# MCU.net
KiCad netlist of a schematic drawn in Altium Designer
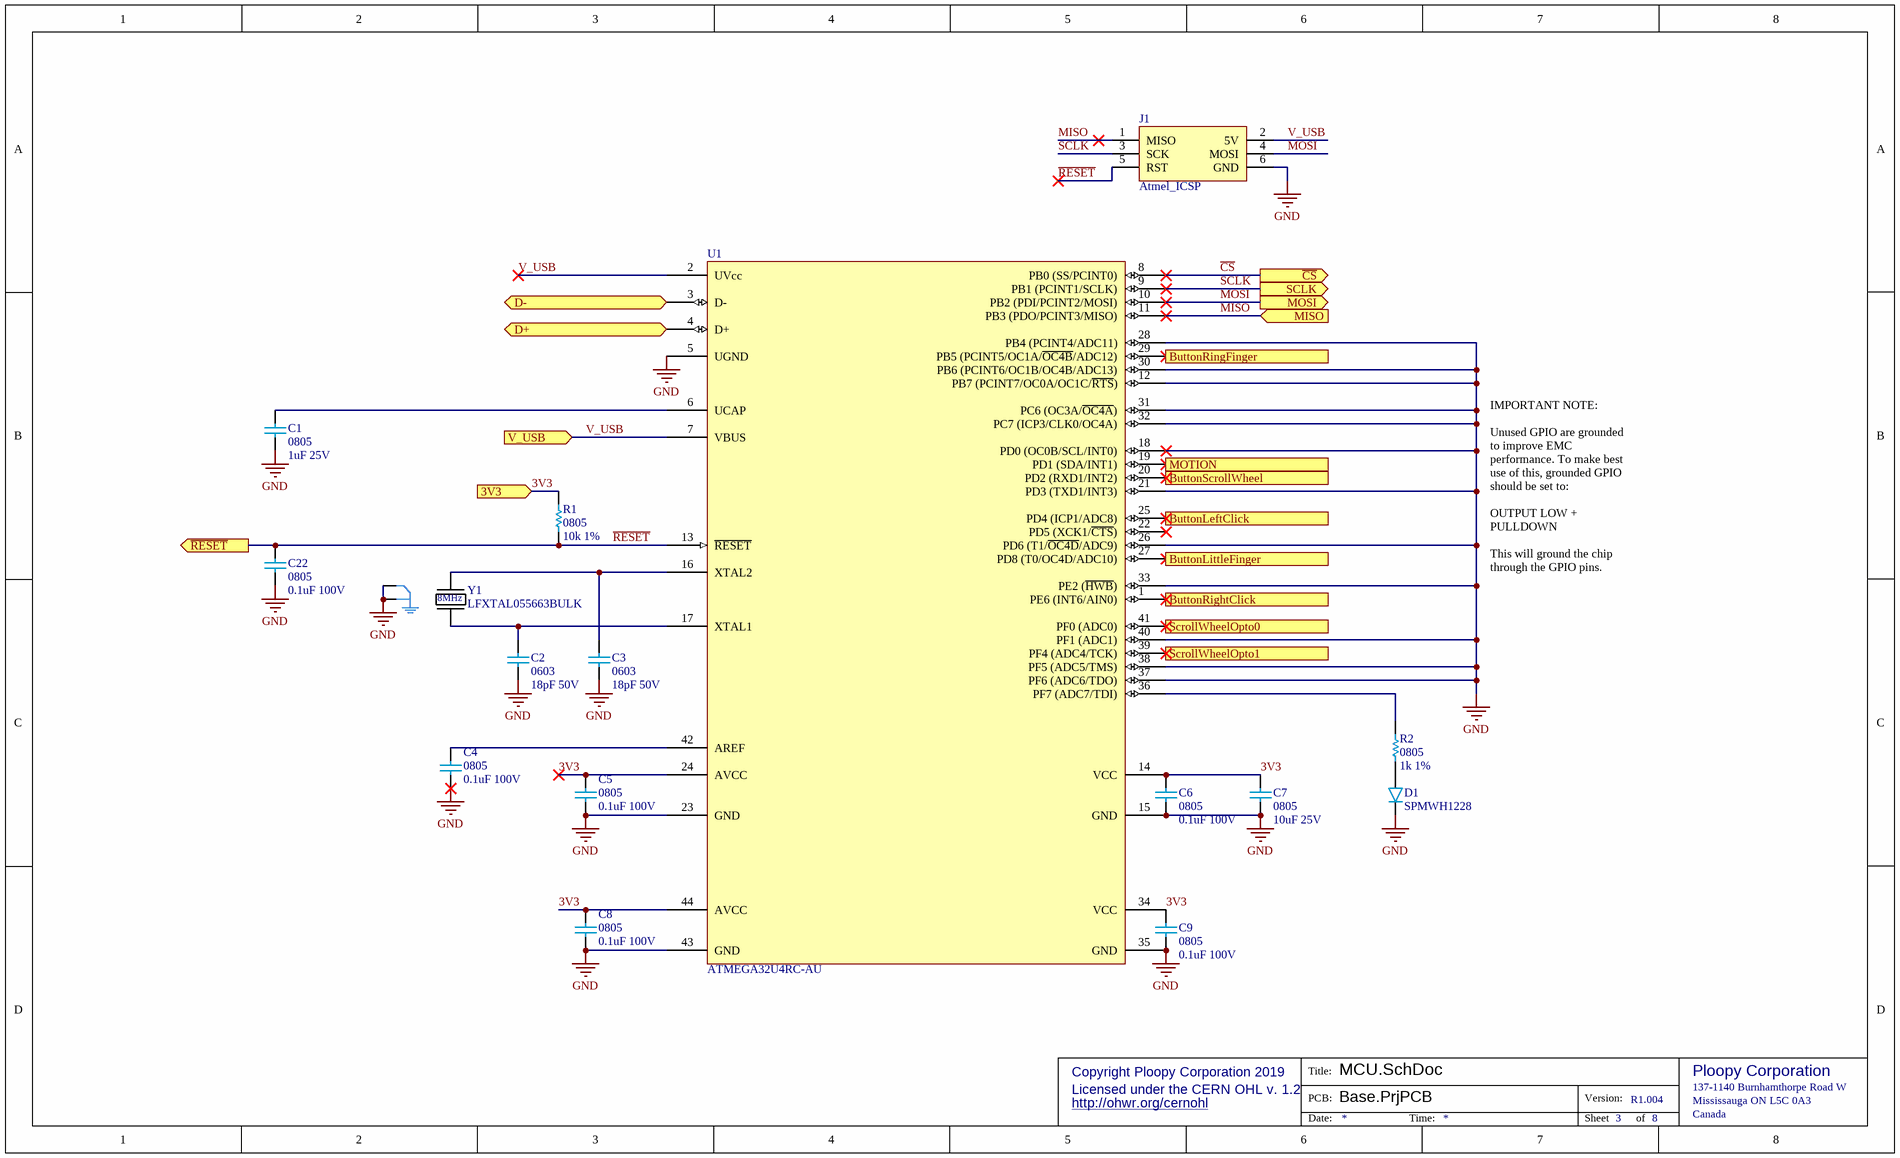
[diagram p0: MCU.SchDoc]

(export (version "E")
  (design (tool "Eeschema 10.0.6"))
  (components
    (comp (ref "C1")
      (value "0805")
      (footprint "0805")
      (description "0805, X5R or better")
      (fields (field (name "ALTIUM_VALUE") "1uF 25V"))
      (libsource (lib "Chip_Passives") (part "Cap 1uF 25V"))
    )
    (comp (ref "C2")
      (value "0603")
      (footprint "0603")
      (description "0603, C0G or better")
      (fields (field (name "ALTIUM_VALUE") "18pF 50V"))
      (libsource (lib "Chip_Passives") (part "Cap 18pF 50V"))
    )
    (comp (ref "C3")
      (value "0603")
      (footprint "0603")
      (description "0603, C0G or better")
      (fields (field (name "ALTIUM_VALUE") "18pF 50V"))
      (libsource (lib "Chip_Passives") (part "Cap 18pF 50V"))
    )
    (comp (ref "C4")
      (value "0805")
      (footprint "0805")
      (description "0805, X5R or better")
      (fields (field (name "ALTIUM_VALUE") "0.1uF 100V"))
      (libsource (lib "Chip_Passives") (part "Cap 0.1uF 100V"))
    )
    (comp (ref "C5")
      (value "0805")
      (footprint "0805")
      (description "0805, X5R or better")
      (fields (field (name "ALTIUM_VALUE") "0.1uF 100V"))
      (libsource (lib "Chip_Passives") (part "Cap 0.1uF 100V"))
    )
    (comp (ref "C6")
      (value "0805")
      (footprint "0805")
      (description "0805, X5R or better")
      (fields (field (name "ALTIUM_VALUE") "0.1uF 100V"))
      (libsource (lib "Chip_Passives") (part "Cap 0.1uF 100V"))
    )
    (comp (ref "C7")
      (value "0805")
      (footprint "0805")
      (description "0805, X5R or better")
      (fields (field (name "ALTIUM_VALUE") "10uF 25V"))
      (libsource (lib "Chip_Passives") (part "Cap 10uF 25V"))
    )
    (comp (ref "C8")
      (value "0805")
      (footprint "0805")
      (description "0805, X5R or better")
      (fields (field (name "ALTIUM_VALUE") "0.1uF 100V"))
      (libsource (lib "Chip_Passives") (part "Cap 0.1uF 100V"))
    )
    (comp (ref "C9")
      (value "0805")
      (footprint "0805")
      (description "0805, X5R or better")
      (fields (field (name "ALTIUM_VALUE") "0.1uF 100V"))
      (libsource (lib "Chip_Passives") (part "Cap 0.1uF 100V"))
    )
    (comp (ref "C22")
      (value "0805")
      (footprint "0805")
      (description "0805, X5R or better")
      (fields (field (name "ALTIUM_VALUE") "0.1uF 100V"))
      (libsource (lib "Chip_Passives") (part "Cap 0.1uF 100V"))
    )
    (comp (ref "D1")
      (value "SPMWH1228")
      (footprint "SPMWH1228")
      (description "3V/0.5W white LED, 2.8mm x 3.5mm")
      (libsource (lib "LEDs") (part "SPMWH1228"))
    )
    (comp (ref "J1")
      (value "Atmel_ICSP")
      (footprint "6x2")
      (description "6-pin 0.100\" ICSP header")
      (libsource (lib "Connectors") (part "Atmel_ICSP"))
    )
    (comp (ref "R1")
      (value "0805")
      (footprint "0805")
      (description "Chip resistor")
      (fields (field (name "ALTIUM_VALUE") "10k 1%"))
      (libsource (lib "Chip_Passives") (part "Res 10k 1% 0805"))
    )
    (comp (ref "R2")
      (value "0805")
      (footprint "0805")
      (description "Chip resistor, 1/8W 100PPM")
      (fields (field (name "ALTIUM_VALUE") "1k 1%"))
      (libsource (lib "Chip_Passives") (part "Res 1k 1% 0805"))
    )
    (comp (ref "U1")
      (value "ATMEGA32U4RC-AU")
      (footprint "ATmega32U4 - TQFP80P1200X1200X120-44N")
      (description "IC MCU 8BIT 32KB FLASH 44TQFP")
      (libsource (lib "MCUs") (part "ATMEGA32U4RC-AU"))
    )
    (comp (ref "Y1")
      (value "LFXTAL055663BULK")
      (footprint "LFXTAL055663BULK")
      (description "8MHz ±20ppm Crystal 18pF 150 Ohms 4-SMD, No Lead")
      (libsource (lib "Crystals") (part "LFXTAL055663BULK"))
    )
  )
  (nets
    (net (code "1") (name "/3V3") (class "Default")
      (node (ref "C5") (pin "2") (pinfunction "2_2") (pintype "passive"))
      (node (ref "C6") (pin "2") (pinfunction "2_2") (pintype "passive"))
      (node (ref "C7") (pin "2") (pinfunction "2_2") (pintype "passive"))
      (node (ref "C8") (pin "2") (pinfunction "2_2") (pintype "passive"))
      (node (ref "C9") (pin "2") (pinfunction "2_2") (pintype "passive"))
      (node (ref "R1") (pin "2") (pinfunction "2_2") (pintype "passive"))
      (node (ref "U1") (pin "14") (pinfunction "VCC_14") (pintype "power_in"))
      (node (ref "U1") (pin "24") (pinfunction "AVCC_24") (pintype "power_in"))
      (node (ref "U1") (pin "34") (pinfunction "VCC_34") (pintype "power_in"))
      (node (ref "U1") (pin "44") (pinfunction "AVCC_44") (pintype "power_in"))
    )
    (net (code "2") (name "/ButtonLeftClick") (class "Default")
      (node (ref "U1") (pin "25") (pinfunction "PD4_(ICP1/ADC8)_25") (pintype "bidirectional+no_connect"))
    )
    (net (code "3") (name "/ButtonLittleFinger") (class "Default")
      (node (ref "U1") (pin "27") (pinfunction "PD8_(T0/OC4D/ADC10)_27") (pintype "bidirectional+no_connect"))
    )
    (net (code "4") (name "/ButtonRightClick") (class "Default")
      (node (ref "U1") (pin "1") (pinfunction "PE6_(INT6/AIN0)_1") (pintype "bidirectional+no_connect"))
    )
    (net (code "5") (name "/ButtonRingFinger") (class "Default")
      (node (ref "U1") (pin "29") (pinfunction "PB5_(PCINT5/OC1A/~{OC4B}/ADC12)_29") (pintype "bidirectional+no_connect"))
    )
    (net (code "6") (name "/ButtonScrollWheel") (class "Default")
      (node (ref "U1") (pin "20") (pinfunction "PD2_(RXD1/INT2)_20") (pintype "bidirectional+no_connect"))
    )
    (net (code "7") (name "/D+") (class "Default")
      (node (ref "U1") (pin "4") (pinfunction "D+_4") (pintype "bidirectional"))
    )
    (net (code "8") (name "/D-") (class "Default")
      (node (ref "U1") (pin "3") (pinfunction "D-_3") (pintype "bidirectional"))
    )
    (net (code "9") (name "/MISO") (class "Default")
      (node (ref "J1") (pin "1") (pinfunction "MISO_1") (pintype "passive"))
      (node (ref "U1") (pin "11") (pinfunction "PB3_(PDO/PCINT3/MISO)_11") (pintype "bidirectional"))
    )
    (net (code "10") (name "/MOSI") (class "Default")
      (node (ref "J1") (pin "4") (pinfunction "MOSI_4") (pintype "passive"))
      (node (ref "U1") (pin "10") (pinfunction "PB2_(PDI/PCINT2/MOSI)_10") (pintype "bidirectional"))
    )
    (net (code "11") (name "/MOTION") (class "Default")
      (node (ref "U1") (pin "19") (pinfunction "PD1_(SDA/INT1)_19") (pintype "bidirectional+no_connect"))
    )
    (net (code "12") (name "/SCLK") (class "Default")
      (node (ref "J1") (pin "3") (pinfunction "SCK_3") (pintype "passive"))
      (node (ref "U1") (pin "9") (pinfunction "PB1_(PCINT1/SCLK)_9") (pintype "bidirectional"))
    )
    (net (code "13") (name "/ScrollWheelOpto0") (class "Default")
      (node (ref "U1") (pin "41") (pinfunction "PF0_(ADC0)_41") (pintype "bidirectional+no_connect"))
    )
    (net (code "14") (name "/ScrollWheelOpto1") (class "Default")
      (node (ref "U1") (pin "39") (pinfunction "PF4_(ADC4/TCK)_39") (pintype "bidirectional+no_connect"))
    )
    (net (code "15") (name "/V_USB") (class "Default")
      (node (ref "J1") (pin "2") (pinfunction "5V_2") (pintype "passive"))
      (node (ref "U1") (pin "2") (pinfunction "UVcc_2") (pintype "power_in"))
      (node (ref "U1") (pin "7") (pinfunction "VBUS_7") (pintype "power_in"))
    )
    (net (code "16") (name "/~{CS}") (class "Default")
      (node (ref "U1") (pin "8") (pinfunction "PB0_(SS/PCINT0)_8") (pintype "bidirectional+no_connect"))
    )
    (net (code "17") (name "/~{RESET}") (class "Default")
      (node (ref "C22") (pin "2") (pinfunction "2_2") (pintype "passive"))
      (node (ref "J1") (pin "5") (pinfunction "RST_5") (pintype "passive"))
      (node (ref "R1") (pin "1") (pinfunction "1_1") (pintype "passive"))
      (node (ref "U1") (pin "13") (pinfunction "~{RESET}_13") (pintype "input"))
    )
    (net (code "18") (name "GND") (class "Default")
      (node (ref "C1") (pin "1") (pinfunction "1_1") (pintype "passive"))
      (node (ref "C2") (pin "1") (pinfunction "1_1") (pintype "passive"))
      (node (ref "C22") (pin "1") (pinfunction "1_1") (pintype "passive"))
      (node (ref "C3") (pin "1") (pinfunction "1_1") (pintype "passive"))
      (node (ref "C4") (pin "1") (pinfunction "1_1") (pintype "passive"))
      (node (ref "C5") (pin "1") (pinfunction "1_1") (pintype "passive"))
      (node (ref "C6") (pin "1") (pinfunction "1_1") (pintype "passive"))
      (node (ref "C7") (pin "1") (pinfunction "1_1") (pintype "passive"))
      (node (ref "C8") (pin "1") (pinfunction "1_1") (pintype "passive"))
      (node (ref "C9") (pin "1") (pinfunction "1_1") (pintype "passive"))
      (node (ref "D1") (pin "2") (pinfunction "C_2") (pintype "passive"))
      (node (ref "J1") (pin "6") (pinfunction "GND_6") (pintype "passive"))
      (node (ref "U1") (pin "12") (pinfunction "PB7_(PCINT7/OC0A/OC1C/~{RTS})_12") (pintype "bidirectional"))
      (node (ref "U1") (pin "15") (pinfunction "GND_15") (pintype "passive"))
      (node (ref "U1") (pin "18") (pinfunction "PD0_(OC0B/SCL/INT0)_18") (pintype "bidirectional"))
      (node (ref "U1") (pin "21") (pinfunction "PD3_(TXD1/INT3)_21") (pintype "bidirectional"))
      (node (ref "U1") (pin "23") (pinfunction "GND_23") (pintype "passive"))
      (node (ref "U1") (pin "26") (pinfunction "PD6_(T1/~{OC4D}/ADC9)_26") (pintype "bidirectional"))
      (node (ref "U1") (pin "28") (pinfunction "PB4_(PCINT4/ADC11)_28") (pintype "bidirectional"))
      (node (ref "U1") (pin "30") (pinfunction "PB6_(PCINT6/OC1B/OC4B/ADC13)_30") (pintype "bidirectional"))
      (node (ref "U1") (pin "31") (pinfunction "PC6_(OC3A/~{OC4A})_31") (pintype "bidirectional"))
      (node (ref "U1") (pin "32") (pinfunction "PC7_(ICP3/CLK0/OC4A)_32") (pintype "bidirectional"))
      (node (ref "U1") (pin "33") (pinfunction "PE2_(~{HWB})_33") (pintype "bidirectional"))
      (node (ref "U1") (pin "35") (pinfunction "GND_35") (pintype "passive"))
      (node (ref "U1") (pin "37") (pinfunction "PF6_(ADC6/TDO)_37") (pintype "bidirectional"))
      (node (ref "U1") (pin "38") (pinfunction "PF5_(ADC5/TMS)_38") (pintype "bidirectional"))
      (node (ref "U1") (pin "40") (pinfunction "PF1_(ADC1)_40") (pintype "bidirectional"))
      (node (ref "U1") (pin "43") (pinfunction "GND_43") (pintype "passive"))
      (node (ref "U1") (pin "5") (pinfunction "UGND_5") (pintype "passive"))
      (node (ref "Y1") (pin "2") (pinfunction "2_2") (pintype "passive"))
      (node (ref "Y1") (pin "4") (pinfunction "4_4") (pintype "passive"))
    )
    (net (code "19") (name "Net-(D1-A)") (class "Default")
      (node (ref "D1") (pin "1") (pinfunction "A_1") (pintype "passive"))
      (node (ref "R2") (pin "1") (pinfunction "1_1") (pintype "passive"))
    )
    (net (code "20") (name "Net-(U1-AREF)") (class "Default")
      (node (ref "C4") (pin "2") (pinfunction "2_2") (pintype "passive"))
      (node (ref "U1") (pin "42") (pinfunction "AREF_42") (pintype "passive"))
    )
    (net (code "21") (name "Net-(U1-PF7_(ADC7{slash}TDI))") (class "Default")
      (node (ref "R2") (pin "2") (pinfunction "2_2") (pintype "passive"))
      (node (ref "U1") (pin "36") (pinfunction "PF7_(ADC7/TDI)_36") (pintype "bidirectional"))
    )
    (net (code "22") (name "Net-(U1-UCAP)") (class "Default")
      (node (ref "C1") (pin "2") (pinfunction "2_2") (pintype "passive"))
      (node (ref "U1") (pin "6") (pinfunction "UCAP_6") (pintype "passive"))
    )
    (net (code "23") (name "Net-(U1-XTAL1)") (class "Default")
      (node (ref "C2") (pin "2") (pinfunction "2_2") (pintype "passive"))
      (node (ref "U1") (pin "17") (pinfunction "XTAL1_17") (pintype "passive"))
      (node (ref "Y1") (pin "3") (pinfunction "3_3") (pintype "passive"))
    )
    (net (code "24") (name "Net-(U1-XTAL2)") (class "Default")
      (node (ref "C3") (pin "2") (pinfunction "2_2") (pintype "passive"))
      (node (ref "U1") (pin "16") (pinfunction "XTAL2_16") (pintype "passive"))
      (node (ref "Y1") (pin "1") (pinfunction "1_1") (pintype "passive"))
    )
    (net (code "25") (name "unconnected-(U1-PD5_(XCK1{slash}~{CTS})-Pad22)") (class "Default")
      (node (ref "U1") (pin "22") (pinfunction "PD5_(XCK1/~{CTS})_22") (pintype "bidirectional+no_connect"))
    )
  )
)
